# BSE_APPS_Error_Detection.net
KiCad netlist of a schematic drawn in Altium Designer
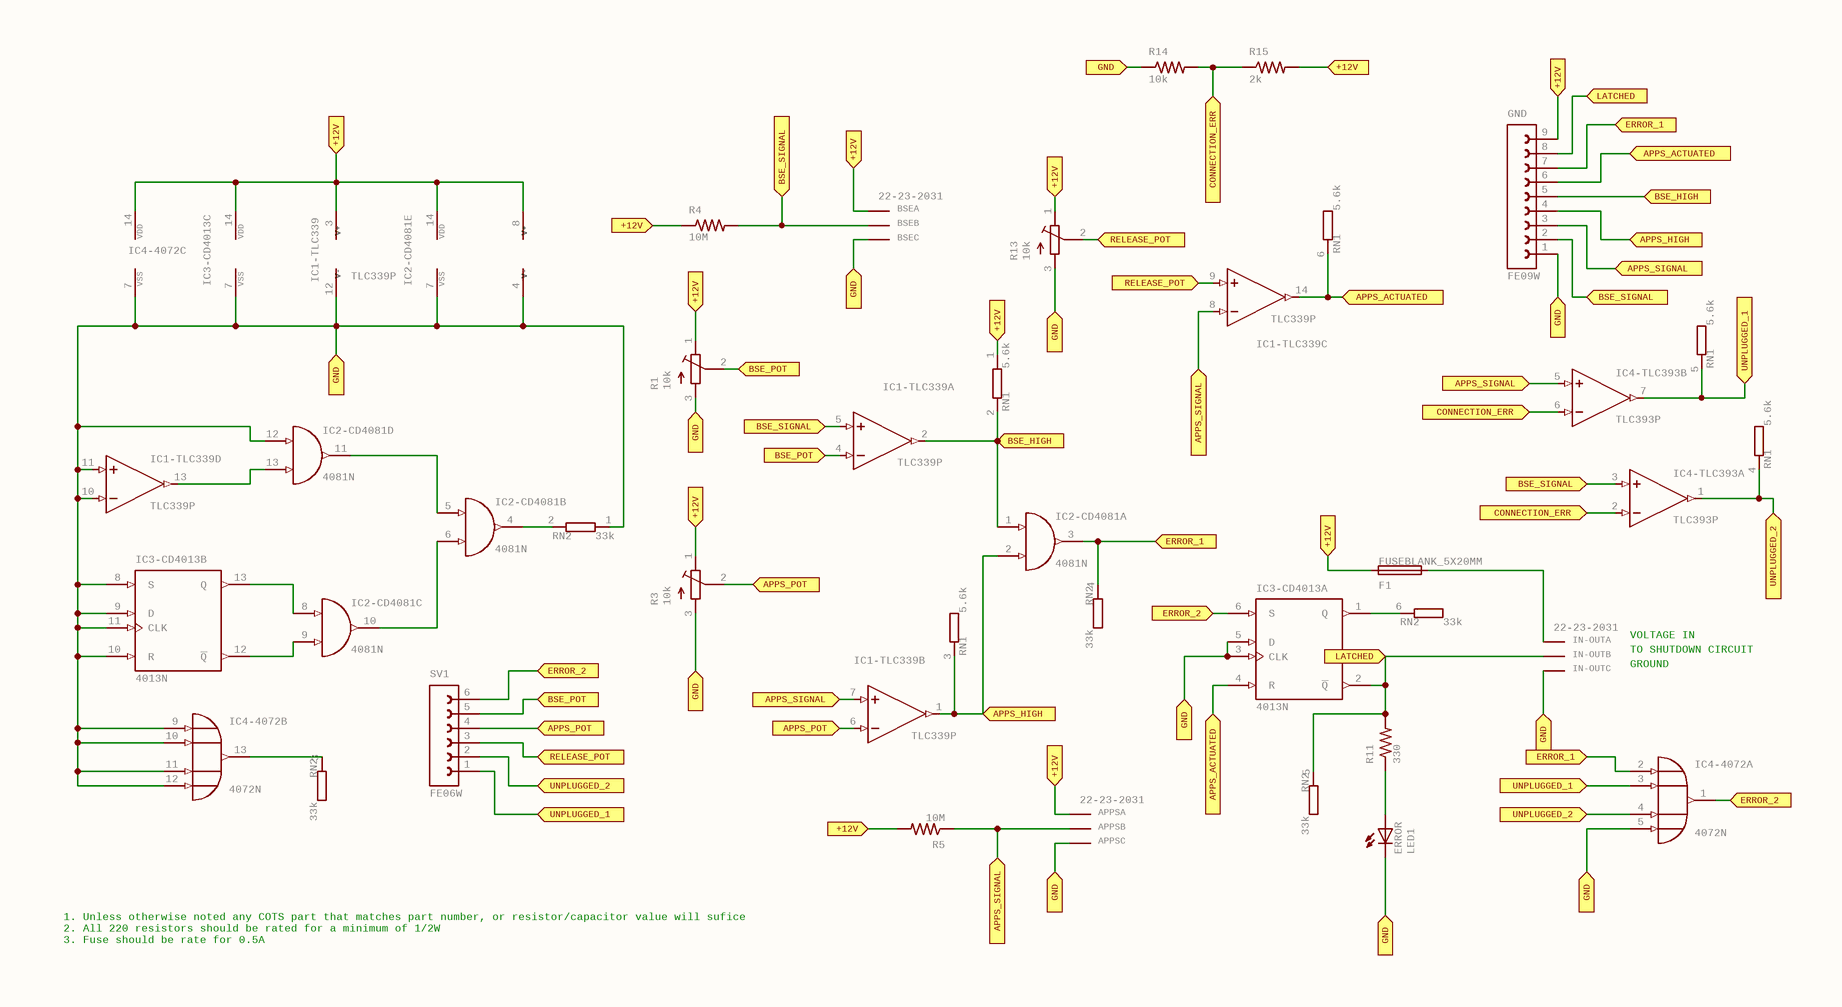
[diagram p0: BSE_APPS_Error_Detection.SchDoc]

(export (version "E")
  (design (tool "Eeschema 10.0.6"))
  (components
    (comp (ref "APPS")
      (value "22-23-2031")
      (footprint "22-23-2031")
      (description ".100\" (2.54mm) Center Header - 3 Pin")
      (fields (field (name "MF") "MOLEX"))
      (libsource (lib "con-molex") (part "22-23-2031"))
    )
    (comp (ref "BSE")
      (value "22-23-2031")
      (footprint "22-23-2031")
      (description ".100\" (2.54mm) Center Header - 3 Pin")
      (fields (field (name "MF") "MOLEX"))
      (libsource (lib "con-molex") (part "22-23-2031"))
    )
    (comp (ref "ERROR") (value "LED1") (footprint "LED5MM") (libsource (lib "led") (part "LED5MM")))
    (comp (ref "F1")
      (value "FUSEBLANK_5X20MM")
      (footprint "FUSE_HOLDER_5X20MM")
      (description "Fuse")
      (fields (field (name "MF") "MF") (field (name "MPN") "MPN"))
      (libsource (lib "fuse") (part "FUSEBLANK_5X20MM"))
    )
    (comp (ref "GND")
      (value "FE09W")
      (footprint "FE09W")
      (description "FEMALE HEADER")
      (fields (field (name "MF") "MF") (field (name "MPN") "MPN") (field (name "LIBRARYNAME") "con-lsta"))
      (libsource (lib "con-lsta") (part "FE09W"))
    )
    (comp (ref "IC1-TLC339")
      (value "TLC339P")
      (footprint "DIL14")
      (description "COMPARATOR")
      (fields (field (name "V+") "V+") (field (name "V-") "V-"))
      (libsource (lib "linear") (part "TLC339P"))
    )
    (comp (ref "IC2-CD4081")
      (value "4081N")
      (footprint "DIL14")
      (description "Quad 2-input AND")
      (fields (field (name "VDD") "VDD") (field (name "VSS") "VSS"))
      (libsource (lib "40xx") (part "4081N"))
    )
    (comp (ref "IC3-CD4013")
      (value "4013N")
      (footprint "DIL14")
      (description "Dual D FLIP FLOP, set/reset")
      (fields (field (name "VDD") "VDD") (field (name "VSS") "VSS"))
      (libsource (lib "40xx") (part "4013N"))
    )
    (comp (ref "IC4-4072")
      (value "4072N")
      (footprint "DIL14")
      (description "Dual 4-input OR")
      (fields (field (name "VDD") "VDD") (field (name "VSS") "VSS"))
      (libsource (lib "40xx") (part "4072N"))
    )
    (comp (ref "IC4-TLC393")
      (value "TLC393P")
      (footprint "DIL08")
      (description "COMPARATOR")
      (fields (field (name "V+") "V+") (field (name "V-") "V-"))
      (libsource (lib "linear") (part "TLC393P"))
    )
    (comp (ref "IN-OUT")
      (value "22-23-2031")
      (footprint "22-23-2031")
      (description ".100\" (2.54mm) Center Header - 3 Pin")
      (fields (field (name "MF") "MOLEX"))
      (libsource (lib "con-molex") (part "22-23-2031"))
    )
    (comp (ref "R1")
      (value "10k")
      (footprint "RTRIM3006P")
      (description "Trimm resistor")
      (libsource (lib "rcl") (part "R-TRIMM3006P"))
    )
    (comp (ref "R3")
      (value "10k")
      (footprint "RTRIM3006P")
      (description "Trimm resistor")
      (libsource (lib "rcl") (part "R-TRIMM3006P"))
    )
    (comp (ref "R4")
      (value "10M")
      (footprint "0207/10")
      (description "RESISTOR, American symbol")
      (libsource (lib "resistor") (part "R-US_0207/10"))
    )
    (comp (ref "R5")
      (value "10M")
      (footprint "0207/10")
      (description "RESISTOR, American symbol")
      (libsource (lib "resistor") (part "R-US_0207/10"))
    )
    (comp (ref "R11")
      (value "330")
      (footprint "0207/10")
      (description "RESISTOR, American symbol")
      (libsource (lib "resistor") (part "R-US_0207/10"))
    )
    (comp (ref "R13")
      (value "10k")
      (footprint "RTRIM3006P")
      (description "Trimm resistor")
      (libsource (lib "rcl") (part "R-TRIMM3006P"))
    )
    (comp (ref "R14")
      (value "10k")
      (footprint "0207/10")
      (description "RESISTOR, American symbol")
      (libsource (lib "resistor") (part "R-US_0207/10"))
    )
    (comp (ref "R15")
      (value "2k")
      (footprint "0207/10")
      (description "RESISTOR, American symbol")
      (libsource (lib "resistor") (part "R-US_0207/10"))
    )
    (comp (ref "RN1")
      (value "5.6k")
      (footprint "SIL6")
      (description "SIL RESISTOR")
      (fields (field (name "PART") "RN1") (field (name "MF") "MF") (field (name "MPN") "MPN"))
      (libsource (lib "resistor-sil") (part "GE05RP"))
    )
    (comp (ref "RN2")
      (value "33k")
      (footprint "SIL6")
      (description "SIL RESISTOR")
      (fields (field (name "PART") "RN2") (field (name "MF") "MF") (field (name "MPN") "MPN"))
      (libsource (lib "resistor-sil") (part "GE05RP"))
    )
    (comp (ref "SV1")
      (value "FE06W")
      (footprint "FE06W")
      (description "FEMALE HEADER")
      (fields (field (name "MF") "MF") (field (name "MPN") "MPN") (field (name "LIBRARYNAME") "con-lsta"))
      (libsource (lib "con-lsta") (part "FE06W"))
    )
  )
  (nets
    (net (code "1") (name "/+12V") (class "Default")
      (node (ref "APPS") (pin "1") (pinfunction "S_1") (pintype "passive"))
      (node (ref "BSE") (pin "1") (pinfunction "S_1") (pintype "passive"))
      (node (ref "F1") (pin "1") (pinfunction "1_1") (pintype "passive"))
      (node (ref "GND") (pin "9") (pinfunction "9_9") (pintype "passive"))
      (node (ref "IC1-TLC339") (pin "3") (pinfunction "V+_3") (pintype "power_in"))
      (node (ref "IC2-CD4081") (pin "14") (pinfunction "VDD_14") (pintype "power_in"))
      (node (ref "IC3-CD4013") (pin "14") (pinfunction "VDD_14") (pintype "power_in"))
      (node (ref "IC4-4072") (pin "14") (pinfunction "VDD_14") (pintype "power_in"))
      (node (ref "IC4-TLC393") (pin "8") (pinfunction "V+_8") (pintype "power_in"))
      (node (ref "R1") (pin "1") (pinfunction "E_1") (pintype "passive"))
      (node (ref "R13") (pin "1") (pinfunction "E_1") (pintype "passive"))
      (node (ref "R15") (pin "2") (pinfunction "2_2") (pintype "passive"))
      (node (ref "R3") (pin "1") (pinfunction "E_1") (pintype "passive"))
      (node (ref "R4") (pin "1") (pinfunction "1_1") (pintype "passive"))
      (node (ref "R5") (pin "2") (pinfunction "2_2") (pintype "passive"))
      (node (ref "RN1") (pin "1") (pinfunction "1_1") (pintype "passive"))
    )
    (net (code "2") (name "/APPS_ACTUATED") (class "Default")
      (node (ref "GND") (pin "6") (pinfunction "6_6") (pintype "passive"))
      (node (ref "IC1-TLC339") (pin "14") (pinfunction "OUT_14") (pintype "output"))
      (node (ref "IC3-CD4013") (pin "4") (pinfunction "R_4") (pintype "input"))
      (node (ref "RN1") (pin "6") (pinfunction "2_6") (pintype "passive"))
    )
    (net (code "3") (name "/APPS_HIGH") (class "Default")
      (node (ref "GND") (pin "4") (pinfunction "4_4") (pintype "passive"))
      (node (ref "IC1-TLC339") (pin "1") (pinfunction "OUT_1") (pintype "output"))
      (node (ref "IC2-CD4081") (pin "2") (pinfunction "I1_2") (pintype "input"))
      (node (ref "RN1") (pin "3") (pinfunction "2_3") (pintype "passive"))
    )
    (net (code "4") (name "/APPS_POT") (class "Default")
      (node (ref "IC1-TLC339") (pin "6") (pinfunction "-IN_6") (pintype "input"))
      (node (ref "R3") (pin "2") (pinfunction "S_2") (pintype "passive"))
      (node (ref "SV1") (pin "4") (pinfunction "4_4") (pintype "passive"))
    )
    (net (code "5") (name "/APPS_SIGNAL") (class "Default")
      (node (ref "APPS") (pin "2") (pinfunction "S_2") (pintype "passive"))
      (node (ref "GND") (pin "3") (pinfunction "3_3") (pintype "passive"))
      (node (ref "IC1-TLC339") (pin "7") (pinfunction "+IN_7") (pintype "input"))
      (node (ref "IC1-TLC339") (pin "8") (pinfunction "-IN_8") (pintype "input"))
      (node (ref "IC4-TLC393") (pin "5") (pinfunction "+IN_5") (pintype "input"))
      (node (ref "R5") (pin "1") (pinfunction "1_1") (pintype "passive"))
    )
    (net (code "6") (name "/BSE_HIGH") (class "Default")
      (node (ref "GND") (pin "5") (pinfunction "5_5") (pintype "passive"))
      (node (ref "IC1-TLC339") (pin "2") (pinfunction "OUT_2") (pintype "output"))
      (node (ref "IC2-CD4081") (pin "1") (pinfunction "I0_1") (pintype "input"))
      (node (ref "RN1") (pin "2") (pinfunction "2_2") (pintype "passive"))
    )
    (net (code "7") (name "/BSE_POT") (class "Default")
      (node (ref "IC1-TLC339") (pin "4") (pinfunction "-IN_4") (pintype "input"))
      (node (ref "R1") (pin "2") (pinfunction "S_2") (pintype "passive"))
      (node (ref "SV1") (pin "5") (pinfunction "5_5") (pintype "passive"))
    )
    (net (code "8") (name "/BSE_SIGNAL") (class "Default")
      (node (ref "BSE") (pin "2") (pinfunction "S_2") (pintype "passive"))
      (node (ref "GND") (pin "2") (pinfunction "2_2") (pintype "passive"))
      (node (ref "IC1-TLC339") (pin "5") (pinfunction "+IN_5") (pintype "input"))
      (node (ref "IC4-TLC393") (pin "3") (pinfunction "+IN_3") (pintype "input"))
      (node (ref "R4") (pin "2") (pinfunction "2_2") (pintype "passive"))
    )
    (net (code "9") (name "/CONNECTION_ERR") (class "Default")
      (node (ref "IC4-TLC393") (pin "2") (pinfunction "-IN_2") (pintype "input"))
      (node (ref "IC4-TLC393") (pin "6") (pinfunction "-IN_6") (pintype "input"))
      (node (ref "R14") (pin "2") (pinfunction "2_2") (pintype "passive"))
      (node (ref "R15") (pin "1") (pinfunction "1_1") (pintype "passive"))
    )
    (net (code "10") (name "/ERROR_1") (class "Default")
      (node (ref "GND") (pin "7") (pinfunction "7_7") (pintype "passive"))
      (node (ref "IC2-CD4081") (pin "3") (pinfunction "O_3") (pintype "output"))
      (node (ref "IC4-4072") (pin "2") (pinfunction "I0_2") (pintype "input"))
      (node (ref "RN2") (pin "4") (pinfunction "2_4") (pintype "passive"))
    )
    (net (code "11") (name "/ERROR_2") (class "Default")
      (node (ref "IC3-CD4013") (pin "6") (pinfunction "S_6") (pintype "input"))
      (node (ref "IC4-4072") (pin "1") (pinfunction "O_1") (pintype "output"))
      (node (ref "SV1") (pin "6") (pinfunction "6_6") (pintype "passive"))
    )
    (net (code "12") (name "/GND") (class "Default")
      (node (ref "APPS") (pin "3") (pinfunction "S_3") (pintype "passive"))
      (node (ref "BSE") (pin "3") (pinfunction "S_3") (pintype "passive"))
      (node (ref "ERROR") (pin "K") (pinfunction "C_K") (pintype "passive"))
      (node (ref "GND") (pin "1") (pinfunction "1_1") (pintype "passive"))
      (node (ref "IC1-TLC339") (pin "10") (pinfunction "-IN_10") (pintype "input"))
      (node (ref "IC1-TLC339") (pin "11") (pinfunction "+IN_11") (pintype "input"))
      (node (ref "IC1-TLC339") (pin "12") (pinfunction "V-_12") (pintype "power_in"))
      (node (ref "IC2-CD4081") (pin "12") (pinfunction "I0_12") (pintype "input"))
      (node (ref "IC2-CD4081") (pin "7") (pinfunction "VSS_7") (pintype "power_in"))
      (node (ref "IC3-CD4013") (pin "10") (pinfunction "R_10") (pintype "input"))
      (node (ref "IC3-CD4013") (pin "11") (pinfunction "CLK_11") (pintype "input"))
      (node (ref "IC3-CD4013") (pin "3") (pinfunction "CLK_3") (pintype "input"))
      (node (ref "IC3-CD4013") (pin "5") (pinfunction "D_5") (pintype "input"))
      (node (ref "IC3-CD4013") (pin "7") (pinfunction "VSS_7") (pintype "power_in"))
      (node (ref "IC3-CD4013") (pin "8") (pinfunction "S_8") (pintype "input"))
      (node (ref "IC3-CD4013") (pin "9") (pinfunction "D_9") (pintype "input"))
      (node (ref "IC4-4072") (pin "10") (pinfunction "I1_10") (pintype "input"))
      (node (ref "IC4-4072") (pin "11") (pinfunction "I2_11") (pintype "input"))
      (node (ref "IC4-4072") (pin "12") (pinfunction "I3_12") (pintype "input"))
      (node (ref "IC4-4072") (pin "5") (pinfunction "I3_5") (pintype "input"))
      (node (ref "IC4-4072") (pin "7") (pinfunction "VSS_7") (pintype "power_in"))
      (node (ref "IC4-4072") (pin "9") (pinfunction "I0_9") (pintype "input"))
      (node (ref "IC4-TLC393") (pin "4") (pinfunction "V-_4") (pintype "power_in"))
      (node (ref "IN-OUT") (pin "3") (pinfunction "S_3") (pintype "passive"))
      (node (ref "R1") (pin "3") (pinfunction "A_3") (pintype "passive"))
      (node (ref "R13") (pin "3") (pinfunction "A_3") (pintype "passive"))
      (node (ref "R14") (pin "1") (pinfunction "1_1") (pintype "passive"))
      (node (ref "R3") (pin "3") (pinfunction "A_3") (pintype "passive"))
      (node (ref "RN2") (pin "1") (pinfunction "1_1") (pintype "passive"))
    )
    (net (code "13") (name "/LATCHED") (class "Default")
      (node (ref "GND") (pin "8") (pinfunction "8_8") (pintype "passive"))
      (node (ref "IC3-CD4013") (pin "2") (pinfunction "~{Q}_2") (pintype "output"))
      (node (ref "IN-OUT") (pin "2") (pinfunction "S_2") (pintype "passive"))
      (node (ref "R11") (pin "2") (pinfunction "2_2") (pintype "passive"))
      (node (ref "RN2") (pin "5") (pinfunction "2_5") (pintype "passive"))
    )
    (net (code "14") (name "/RELEASE_POT") (class "Default")
      (node (ref "IC1-TLC339") (pin "9") (pinfunction "+IN_9") (pintype "input"))
      (node (ref "R13") (pin "2") (pinfunction "S_2") (pintype "passive"))
      (node (ref "SV1") (pin "3") (pinfunction "3_3") (pintype "passive"))
    )
    (net (code "15") (name "/UNPLUGGED_1") (class "Default")
      (node (ref "IC4-4072") (pin "3") (pinfunction "I1_3") (pintype "input"))
      (node (ref "IC4-TLC393") (pin "7") (pinfunction "OUT_7") (pintype "output"))
      (node (ref "RN1") (pin "5") (pinfunction "2_5") (pintype "passive"))
      (node (ref "SV1") (pin "1") (pinfunction "1_1") (pintype "passive"))
    )
    (net (code "16") (name "/UNPLUGGED_2") (class "Default")
      (node (ref "IC4-4072") (pin "4") (pinfunction "I2_4") (pintype "input"))
      (node (ref "IC4-TLC393") (pin "1") (pinfunction "OUT_1") (pintype "output"))
      (node (ref "RN1") (pin "4") (pinfunction "2_4") (pintype "passive"))
      (node (ref "SV1") (pin "2") (pinfunction "2_2") (pintype "passive"))
    )
    (net (code "17") (name "Net-(ERROR-PadA)") (class "Default")
      (node (ref "ERROR") (pin "A") (pinfunction "A_A") (pintype "passive"))
      (node (ref "R11") (pin "1") (pinfunction "1_1") (pintype "passive"))
    )
    (net (code "18") (name "Net-(IC1-TLC339D-OUT)") (class "Default")
      (node (ref "IC1-TLC339") (pin "13") (pinfunction "OUT_13") (pintype "output"))
      (node (ref "IC2-CD4081") (pin "13") (pinfunction "I1_13") (pintype "input"))
    )
    (net (code "19") (name "Net-(IC2-CD4081B-I0)") (class "Default")
      (node (ref "IC2-CD4081") (pin "11") (pinfunction "O_11") (pintype "output"))
      (node (ref "IC2-CD4081") (pin "5") (pinfunction "I0_5") (pintype "input"))
    )
    (net (code "20") (name "Net-(IC2-CD4081B-I1)") (class "Default")
      (node (ref "IC2-CD4081") (pin "10") (pinfunction "O_10") (pintype "output"))
      (node (ref "IC2-CD4081") (pin "6") (pinfunction "I1_6") (pintype "input"))
    )
    (net (code "21") (name "Net-(IC2-CD4081B-O)") (class "Default")
      (node (ref "IC2-CD4081") (pin "4") (pinfunction "O_4") (pintype "output"))
      (node (ref "RN2") (pin "2") (pinfunction "2_2") (pintype "passive"))
    )
    (net (code "22") (name "Net-(IC2-CD4081C-I0)") (class "Default")
      (node (ref "IC2-CD4081") (pin "8") (pinfunction "I0_8") (pintype "input"))
      (node (ref "IC3-CD4013") (pin "13") (pinfunction "Q_13") (pintype "output"))
    )
    (net (code "23") (name "Net-(IC2-CD4081C-I1)") (class "Default")
      (node (ref "IC2-CD4081") (pin "9") (pinfunction "I1_9") (pintype "input"))
      (node (ref "IC3-CD4013") (pin "12") (pinfunction "~{Q}_12") (pintype "output"))
    )
    (net (code "24") (name "Net-(IC3-CD4013A-Q)") (class "Default")
      (node (ref "IC3-CD4013") (pin "1") (pinfunction "Q_1") (pintype "output"))
      (node (ref "RN2") (pin "6") (pinfunction "2_6") (pintype "passive"))
    )
    (net (code "25") (name "Net-(IC4-4072B-O)") (class "Default")
      (node (ref "IC4-4072") (pin "13") (pinfunction "O_13") (pintype "output"))
      (node (ref "RN2") (pin "3") (pinfunction "2_3") (pintype "passive"))
    )
    (net (code "26") (name "Net-(IN-OUTA-S)") (class "Default")
      (node (ref "F1") (pin "2") (pinfunction "2_2") (pintype "passive"))
      (node (ref "IN-OUT") (pin "1") (pinfunction "S_1") (pintype "passive"))
    )
  )
)
